# 12_RK3588_MIPI_CSI_HDMI2_1_HDMI.net
KiCad netlist of a schematic drawn in Altium Designer
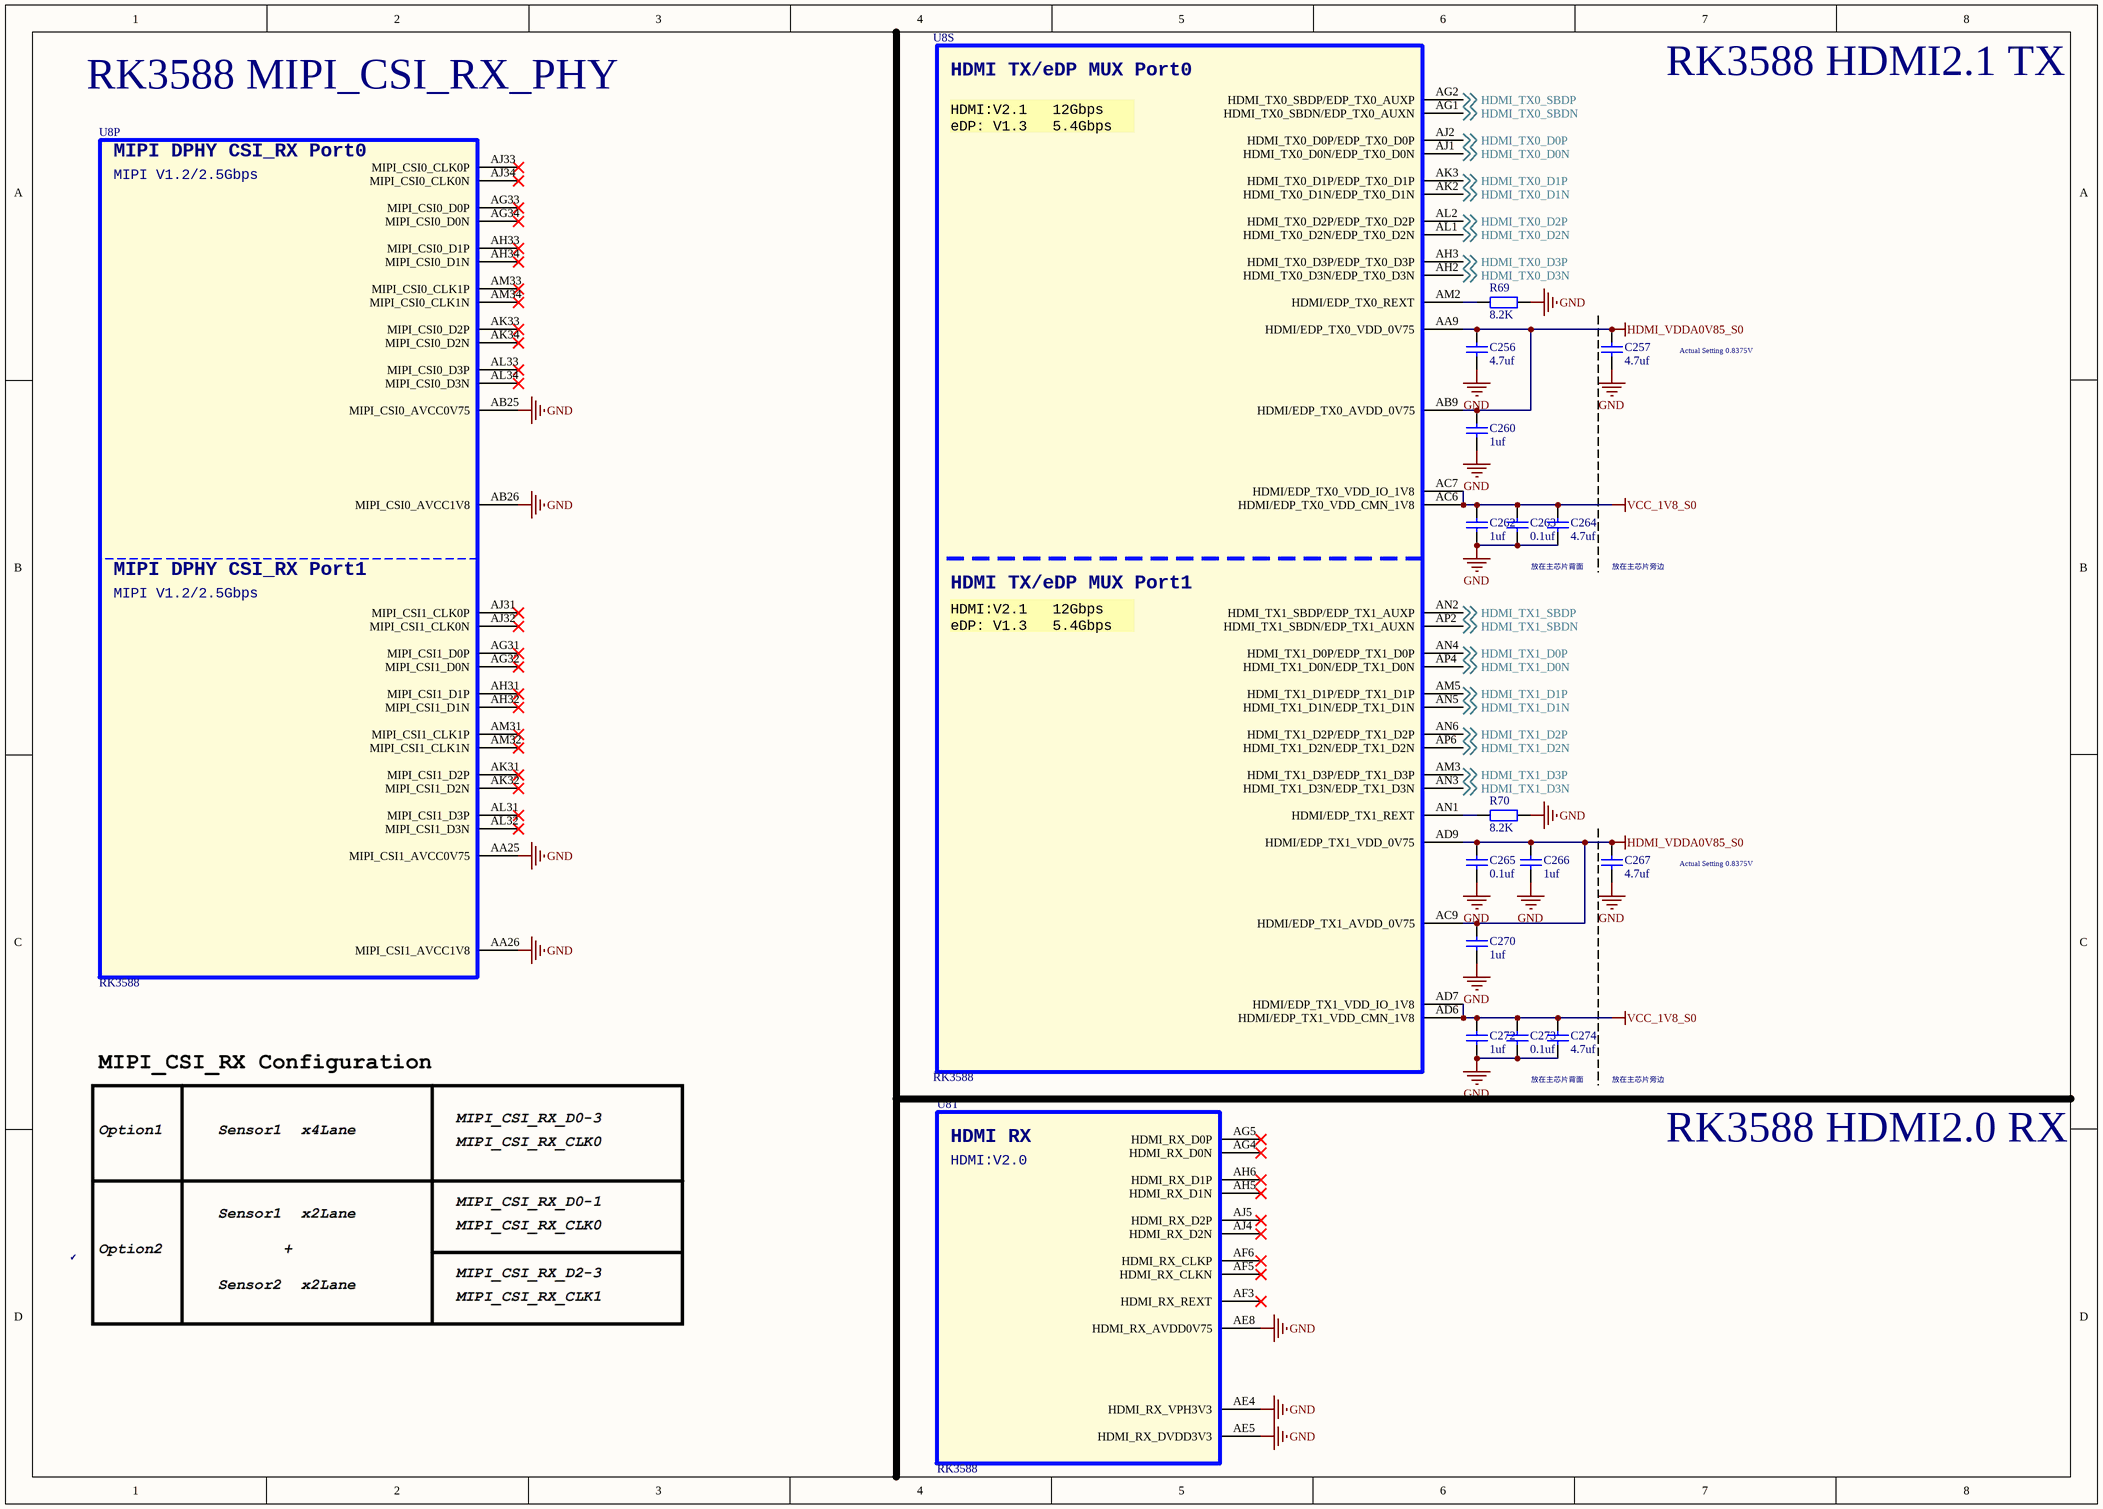
[diagram p0: 12.RK3588_MIPI_CSI_HDMI2.1_HDMI.SchDoc]

(export (version "E")
  (design (tool "Eeschema 10.0.6"))
  (components
    (comp (ref "C256")
      (value "4.7uf")
      (footprint "0.PCB1:C0402_L")
      (description "贴片电容/MLCC电容")
      (libsource (lib "RK3588") (part "C"))
    )
    (comp (ref "C257")
      (value "4.7uf")
      (footprint "0.PCB1:C0402_L")
      (description "贴片电容/MLCC电容")
      (libsource (lib "RK3588") (part "C"))
    )
    (comp (ref "C260")
      (value "1uf")
      (footprint "0.PCB1:C0201_L")
      (description "贴片电容/MLCC电容")
      (libsource (lib "RK3588") (part "C"))
    )
    (comp (ref "C262")
      (value "1uf")
      (footprint "0.PCB1:C0201_L")
      (description "贴片电容/MLCC电容")
      (libsource (lib "RK3588") (part "C"))
    )
    (comp (ref "C263")
      (value "0.1uf")
      (footprint "0.PCB1:C0201_L")
      (description "贴片电容/MLCC电容")
      (libsource (lib "RK3588") (part "C"))
    )
    (comp (ref "C264")
      (value "4.7uf")
      (footprint "0.PCB1:C0201_L")
      (description "贴片电容/MLCC电容")
      (libsource (lib "RK3588") (part "C"))
    )
    (comp (ref "C265")
      (value "0.1uf")
      (footprint "0.PCB1:C0201_L")
      (description "贴片电容/MLCC电容")
      (libsource (lib "RK3588") (part "C"))
    )
    (comp (ref "C266")
      (value "1uf")
      (footprint "0.PCB1:C0201_L")
      (description "贴片电容/MLCC电容")
      (libsource (lib "RK3588") (part "C"))
    )
    (comp (ref "C267")
      (value "4.7uf")
      (footprint "0.PCB1:C0402_L")
      (description "贴片电容/MLCC电容")
      (libsource (lib "RK3588") (part "C"))
    )
    (comp (ref "C270")
      (value "1uf")
      (footprint "0.PCB1:C0201_L")
      (description "贴片电容/MLCC电容")
      (libsource (lib "RK3588") (part "C"))
    )
    (comp (ref "C272")
      (value "1uf")
      (footprint "0.PCB1:C0201_L")
      (description "贴片电容/MLCC电容")
      (libsource (lib "RK3588") (part "C"))
    )
    (comp (ref "C273")
      (value "0.1uf")
      (footprint "0.PCB1:C0201_L")
      (description "贴片电容/MLCC电容")
      (libsource (lib "RK3588") (part "C"))
    )
    (comp (ref "C274")
      (value "4.7uf")
      (footprint "0.PCB1:C0402_L")
      (description "贴片电容/MLCC电容")
      (libsource (lib "RK3588") (part "C"))
    )
    (comp (ref "R69")
      (value "8.2K")
      (footprint "0.PCB1:R0201_L")
      (description "贴片电阻")
      (libsource (lib "RK3588") (part "R"))
    )
    (comp (ref "R70")
      (value "8.2K")
      (footprint "0.PCB1:R0201_L")
      (description "贴片电阻")
      (libsource (lib "RK3588") (part "R"))
    )
    (comp (ref "U8")
      (value "RK3588")
      (footprint "0.PCB1:BGA1088_23R00X23R00X2R00")
      (description "ROCKCHIP SOC")
      (libsource (lib "RK3588") (part "SOC_RK3588"))
    )
  )
  (nets
    (net (code "1") (name "GND") (class "Default")
      (node (ref "C256") (pin "1") (pinfunction "1_1") (pintype "passive"))
      (node (ref "C257") (pin "1") (pinfunction "1_1") (pintype "passive"))
      (node (ref "C260") (pin "1") (pinfunction "1_1") (pintype "passive"))
      (node (ref "C262") (pin "1") (pinfunction "1_1") (pintype "passive"))
      (node (ref "C263") (pin "1") (pinfunction "1_1") (pintype "passive"))
      (node (ref "C264") (pin "1") (pinfunction "1_1") (pintype "passive"))
      (node (ref "C265") (pin "1") (pinfunction "1_1") (pintype "passive"))
      (node (ref "C266") (pin "1") (pinfunction "1_1") (pintype "passive"))
      (node (ref "C267") (pin "1") (pinfunction "1_1") (pintype "passive"))
      (node (ref "C270") (pin "1") (pinfunction "1_1") (pintype "passive"))
      (node (ref "C272") (pin "1") (pinfunction "1_1") (pintype "passive"))
      (node (ref "C273") (pin "1") (pinfunction "1_1") (pintype "passive"))
      (node (ref "C274") (pin "1") (pinfunction "1_1") (pintype "passive"))
      (node (ref "R69") (pin "2") (pinfunction "2_2") (pintype "passive"))
      (node (ref "R70") (pin "2") (pinfunction "2_2") (pintype "passive"))
      (node (ref "U8") (pin "AA25") (pinfunction "MIPI_CSI1_AVCC0V75_AA25") (pintype "passive"))
      (node (ref "U8") (pin "AA26") (pinfunction "MIPI_CSI1_AVCC1V8_AA26") (pintype "passive"))
      (node (ref "U8") (pin "AB25") (pinfunction "MIPI_CSI0_AVCC0V75_AB25") (pintype "passive"))
      (node (ref "U8") (pin "AB26") (pinfunction "MIPI_CSI0_AVCC1V8_AB26") (pintype "passive"))
      (node (ref "U8") (pin "AE4") (pinfunction "HDMI_RX_VPH3V3_AE4") (pintype "passive"))
      (node (ref "U8") (pin "AE5") (pinfunction "HDMI_RX_DVDD3V3_AE5") (pintype "passive"))
      (node (ref "U8") (pin "AE8") (pinfunction "HDMI_RX_AVDD0V75_AE8") (pintype "passive"))
    )
    (net (code "2") (name "HDMI_TX0_D0N") (class "Default")
      (node (ref "U8") (pin "AJ1") (pinfunction "HDMI_TX0_D0N/EDP_TX0_D0N_AJ1") (pintype "passive"))
    )
    (net (code "3") (name "HDMI_TX0_D0P") (class "Default")
      (node (ref "U8") (pin "AJ2") (pinfunction "HDMI_TX0_D0P/EDP_TX0_D0P_AJ2") (pintype "passive"))
    )
    (net (code "4") (name "HDMI_TX0_D1N") (class "Default")
      (node (ref "U8") (pin "AK2") (pinfunction "HDMI_TX0_D1N/EDP_TX0_D1N_AK2") (pintype "passive"))
    )
    (net (code "5") (name "HDMI_TX0_D1P") (class "Default")
      (node (ref "U8") (pin "AK3") (pinfunction "HDMI_TX0_D1P/EDP_TX0_D1P_AK3") (pintype "passive"))
    )
    (net (code "6") (name "HDMI_TX0_D2N") (class "Default")
      (node (ref "U8") (pin "AL1") (pinfunction "HDMI_TX0_D2N/EDP_TX0_D2N_AL1") (pintype "passive"))
    )
    (net (code "7") (name "HDMI_TX0_D2P") (class "Default")
      (node (ref "U8") (pin "AL2") (pinfunction "HDMI_TX0_D2P/EDP_TX0_D2P_AL2") (pintype "passive"))
    )
    (net (code "8") (name "HDMI_TX0_D3N") (class "Default")
      (node (ref "U8") (pin "AH2") (pinfunction "HDMI_TX0_D3N/EDP_TX0_D3N_AH2") (pintype "passive"))
    )
    (net (code "9") (name "HDMI_TX0_D3P") (class "Default")
      (node (ref "U8") (pin "AH3") (pinfunction "HDMI_TX0_D3P/EDP_TX0_D3P_AH3") (pintype "passive"))
    )
    (net (code "10") (name "HDMI_TX0_SBDN") (class "Default")
      (node (ref "U8") (pin "AG1") (pinfunction "HDMI_TX0_SBDN/EDP_TX0_AUXN_AG1") (pintype "passive"))
    )
    (net (code "11") (name "HDMI_TX0_SBDP") (class "Default")
      (node (ref "U8") (pin "AG2") (pinfunction "HDMI_TX0_SBDP/EDP_TX0_AUXP_AG2") (pintype "passive"))
    )
    (net (code "12") (name "HDMI_TX1_D0N") (class "Default")
      (node (ref "U8") (pin "AP4") (pinfunction "HDMI_TX1_D0N/EDP_TX1_D0N_AP4") (pintype "passive"))
    )
    (net (code "13") (name "HDMI_TX1_D0P") (class "Default")
      (node (ref "U8") (pin "AN4") (pinfunction "HDMI_TX1_D0P/EDP_TX1_D0P_AN4") (pintype "passive"))
    )
    (net (code "14") (name "HDMI_TX1_D1N") (class "Default")
      (node (ref "U8") (pin "AN5") (pinfunction "HDMI_TX1_D1N/EDP_TX1_D1N_AN5") (pintype "passive"))
    )
    (net (code "15") (name "HDMI_TX1_D1P") (class "Default")
      (node (ref "U8") (pin "AM5") (pinfunction "HDMI_TX1_D1P/EDP_TX1_D1P_AM5") (pintype "passive"))
    )
    (net (code "16") (name "HDMI_TX1_D2N") (class "Default")
      (node (ref "U8") (pin "AP6") (pinfunction "HDMI_TX1_D2N/EDP_TX1_D2N_AP6") (pintype "passive"))
    )
    (net (code "17") (name "HDMI_TX1_D2P") (class "Default")
      (node (ref "U8") (pin "AN6") (pinfunction "HDMI_TX1_D2P/EDP_TX1_D2P_AN6") (pintype "passive"))
    )
    (net (code "18") (name "HDMI_TX1_D3N") (class "Default")
      (node (ref "U8") (pin "AN3") (pinfunction "HDMI_TX1_D3N/EDP_TX1_D3N_AN3") (pintype "passive"))
    )
    (net (code "19") (name "HDMI_TX1_D3P") (class "Default")
      (node (ref "U8") (pin "AM3") (pinfunction "HDMI_TX1_D3P/EDP_TX1_D3P_AM3") (pintype "passive"))
    )
    (net (code "20") (name "HDMI_TX1_SBDN") (class "Default")
      (node (ref "U8") (pin "AP2") (pinfunction "HDMI_TX1_SBDN/EDP_TX1_AUXN_AP2") (pintype "passive"))
    )
    (net (code "21") (name "HDMI_TX1_SBDP") (class "Default")
      (node (ref "U8") (pin "AN2") (pinfunction "HDMI_TX1_SBDP/EDP_TX1_AUXP_AN2") (pintype "passive"))
    )
    (net (code "22") (name "HDMI_VDDA0V85_S0") (class "Default")
      (node (ref "C256") (pin "2") (pinfunction "2_2") (pintype "passive"))
      (node (ref "C257") (pin "2") (pinfunction "2_2") (pintype "passive"))
      (node (ref "C260") (pin "2") (pinfunction "2_2") (pintype "passive"))
      (node (ref "C265") (pin "2") (pinfunction "2_2") (pintype "passive"))
      (node (ref "C266") (pin "2") (pinfunction "2_2") (pintype "passive"))
      (node (ref "C267") (pin "2") (pinfunction "2_2") (pintype "passive"))
      (node (ref "C270") (pin "2") (pinfunction "2_2") (pintype "passive"))
      (node (ref "U8") (pin "AA9") (pinfunction "HDMI/EDP_TX0_VDD_0V75_AA9") (pintype "passive"))
      (node (ref "U8") (pin "AB9") (pinfunction "HDMI/EDP_TX0_AVDD_0V75_AB9") (pintype "passive"))
      (node (ref "U8") (pin "AC9") (pinfunction "HDMI/EDP_TX1_AVDD_0V75_AC9") (pintype "passive"))
      (node (ref "U8") (pin "AD9") (pinfunction "HDMI/EDP_TX1_VDD_0V75_AD9") (pintype "passive"))
    )
    (net (code "23") (name "Net-(U8S-HDMI{slash}EDP_TX0_REXT)") (class "Default")
      (node (ref "R69") (pin "1") (pinfunction "1_1") (pintype "passive"))
      (node (ref "U8") (pin "AM2") (pinfunction "HDMI/EDP_TX0_REXT_AM2") (pintype "passive"))
    )
    (net (code "24") (name "Net-(U8S-HDMI{slash}EDP_TX1_REXT)") (class "Default")
      (node (ref "R70") (pin "1") (pinfunction "1_1") (pintype "passive"))
      (node (ref "U8") (pin "AN1") (pinfunction "HDMI/EDP_TX1_REXT_AN1") (pintype "passive"))
    )
    (net (code "25") (name "VCC_1V8_S0") (class "Default")
      (node (ref "C262") (pin "2") (pinfunction "2_2") (pintype "passive"))
      (node (ref "C263") (pin "2") (pinfunction "2_2") (pintype "passive"))
      (node (ref "C264") (pin "2") (pinfunction "2_2") (pintype "passive"))
      (node (ref "C272") (pin "2") (pinfunction "2_2") (pintype "passive"))
      (node (ref "C273") (pin "2") (pinfunction "2_2") (pintype "passive"))
      (node (ref "C274") (pin "2") (pinfunction "2_2") (pintype "passive"))
      (node (ref "U8") (pin "AC6") (pinfunction "HDMI/EDP_TX0_VDD_CMN_1V8_AC6") (pintype "passive"))
      (node (ref "U8") (pin "AC7") (pinfunction "HDMI/EDP_TX0_VDD_IO_1V8_AC7") (pintype "passive"))
      (node (ref "U8") (pin "AD6") (pinfunction "HDMI/EDP_TX1_VDD_CMN_1V8_AD6") (pintype "passive"))
      (node (ref "U8") (pin "AD7") (pinfunction "HDMI/EDP_TX1_VDD_IO_1V8_AD7") (pintype "passive"))
    )
    (net (code "26") (name "unconnected-(U8P-MIPI_CSI0_CLK0N-PadAJ34)") (class "Default")
      (node (ref "U8") (pin "AJ34") (pinfunction "MIPI_CSI0_CLK0N_AJ34") (pintype "passive+no_connect"))
    )
    (net (code "27") (name "unconnected-(U8P-MIPI_CSI0_CLK0P-PadAJ33)") (class "Default")
      (node (ref "U8") (pin "AJ33") (pinfunction "MIPI_CSI0_CLK0P_AJ33") (pintype "passive+no_connect"))
    )
    (net (code "28") (name "unconnected-(U8P-MIPI_CSI0_CLK1N-PadAM34)") (class "Default")
      (node (ref "U8") (pin "AM34") (pinfunction "MIPI_CSI0_CLK1N_AM34") (pintype "passive+no_connect"))
    )
    (net (code "29") (name "unconnected-(U8P-MIPI_CSI0_CLK1P-PadAM33)") (class "Default")
      (node (ref "U8") (pin "AM33") (pinfunction "MIPI_CSI0_CLK1P_AM33") (pintype "passive+no_connect"))
    )
    (net (code "30") (name "unconnected-(U8P-MIPI_CSI0_D0N-PadAG34)") (class "Default")
      (node (ref "U8") (pin "AG34") (pinfunction "MIPI_CSI0_D0N_AG34") (pintype "passive+no_connect"))
    )
    (net (code "31") (name "unconnected-(U8P-MIPI_CSI0_D0P-PadAG33)") (class "Default")
      (node (ref "U8") (pin "AG33") (pinfunction "MIPI_CSI0_D0P_AG33") (pintype "passive+no_connect"))
    )
    (net (code "32") (name "unconnected-(U8P-MIPI_CSI0_D1N-PadAH34)") (class "Default")
      (node (ref "U8") (pin "AH34") (pinfunction "MIPI_CSI0_D1N_AH34") (pintype "passive+no_connect"))
    )
    (net (code "33") (name "unconnected-(U8P-MIPI_CSI0_D1P-PadAH33)") (class "Default")
      (node (ref "U8") (pin "AH33") (pinfunction "MIPI_CSI0_D1P_AH33") (pintype "passive+no_connect"))
    )
    (net (code "34") (name "unconnected-(U8P-MIPI_CSI0_D2N-PadAK34)") (class "Default")
      (node (ref "U8") (pin "AK34") (pinfunction "MIPI_CSI0_D2N_AK34") (pintype "passive+no_connect"))
    )
    (net (code "35") (name "unconnected-(U8P-MIPI_CSI0_D2P-PadAK33)") (class "Default")
      (node (ref "U8") (pin "AK33") (pinfunction "MIPI_CSI0_D2P_AK33") (pintype "passive+no_connect"))
    )
    (net (code "36") (name "unconnected-(U8P-MIPI_CSI0_D3N-PadAL34)") (class "Default")
      (node (ref "U8") (pin "AL34") (pinfunction "MIPI_CSI0_D3N_AL34") (pintype "passive+no_connect"))
    )
    (net (code "37") (name "unconnected-(U8P-MIPI_CSI0_D3P-PadAL33)") (class "Default")
      (node (ref "U8") (pin "AL33") (pinfunction "MIPI_CSI0_D3P_AL33") (pintype "passive+no_connect"))
    )
    (net (code "38") (name "unconnected-(U8P-MIPI_CSI1_CLK0N-PadAJ32)") (class "Default")
      (node (ref "U8") (pin "AJ32") (pinfunction "MIPI_CSI1_CLK0N_AJ32") (pintype "passive+no_connect"))
    )
    (net (code "39") (name "unconnected-(U8P-MIPI_CSI1_CLK0P-PadAJ31)") (class "Default")
      (node (ref "U8") (pin "AJ31") (pinfunction "MIPI_CSI1_CLK0P_AJ31") (pintype "passive+no_connect"))
    )
    (net (code "40") (name "unconnected-(U8P-MIPI_CSI1_CLK1N-PadAM32)") (class "Default")
      (node (ref "U8") (pin "AM32") (pinfunction "MIPI_CSI1_CLK1N_AM32") (pintype "passive+no_connect"))
    )
    (net (code "41") (name "unconnected-(U8P-MIPI_CSI1_CLK1P-PadAM31)") (class "Default")
      (node (ref "U8") (pin "AM31") (pinfunction "MIPI_CSI1_CLK1P_AM31") (pintype "passive+no_connect"))
    )
    (net (code "42") (name "unconnected-(U8P-MIPI_CSI1_D0N-PadAG32)") (class "Default")
      (node (ref "U8") (pin "AG32") (pinfunction "MIPI_CSI1_D0N_AG32") (pintype "passive+no_connect"))
    )
    (net (code "43") (name "unconnected-(U8P-MIPI_CSI1_D0P-PadAG31)") (class "Default")
      (node (ref "U8") (pin "AG31") (pinfunction "MIPI_CSI1_D0P_AG31") (pintype "passive+no_connect"))
    )
    (net (code "44") (name "unconnected-(U8P-MIPI_CSI1_D1N-PadAH32)") (class "Default")
      (node (ref "U8") (pin "AH32") (pinfunction "MIPI_CSI1_D1N_AH32") (pintype "passive+no_connect"))
    )
    (net (code "45") (name "unconnected-(U8P-MIPI_CSI1_D1P-PadAH31)") (class "Default")
      (node (ref "U8") (pin "AH31") (pinfunction "MIPI_CSI1_D1P_AH31") (pintype "passive+no_connect"))
    )
    (net (code "46") (name "unconnected-(U8P-MIPI_CSI1_D2N-PadAK32)") (class "Default")
      (node (ref "U8") (pin "AK32") (pinfunction "MIPI_CSI1_D2N_AK32") (pintype "passive+no_connect"))
    )
    (net (code "47") (name "unconnected-(U8P-MIPI_CSI1_D2P-PadAK31)") (class "Default")
      (node (ref "U8") (pin "AK31") (pinfunction "MIPI_CSI1_D2P_AK31") (pintype "passive+no_connect"))
    )
    (net (code "48") (name "unconnected-(U8P-MIPI_CSI1_D3N-PadAL32)") (class "Default")
      (node (ref "U8") (pin "AL32") (pinfunction "MIPI_CSI1_D3N_AL32") (pintype "passive+no_connect"))
    )
    (net (code "49") (name "unconnected-(U8P-MIPI_CSI1_D3P-PadAL31)") (class "Default")
      (node (ref "U8") (pin "AL31") (pinfunction "MIPI_CSI1_D3P_AL31") (pintype "passive+no_connect"))
    )
    (net (code "50") (name "unconnected-(U8T-HDMI_RX_CLKN-PadAF5)") (class "Default")
      (node (ref "U8") (pin "AF5") (pinfunction "HDMI_RX_CLKN_AF5") (pintype "passive+no_connect"))
    )
    (net (code "51") (name "unconnected-(U8T-HDMI_RX_CLKP-PadAF6)") (class "Default")
      (node (ref "U8") (pin "AF6") (pinfunction "HDMI_RX_CLKP_AF6") (pintype "passive+no_connect"))
    )
    (net (code "52") (name "unconnected-(U8T-HDMI_RX_D0N-PadAG4)") (class "Default")
      (node (ref "U8") (pin "AG4") (pinfunction "HDMI_RX_D0N_AG4") (pintype "passive+no_connect"))
    )
    (net (code "53") (name "unconnected-(U8T-HDMI_RX_D0P-PadAG5)") (class "Default")
      (node (ref "U8") (pin "AG5") (pinfunction "HDMI_RX_D0P_AG5") (pintype "passive+no_connect"))
    )
    (net (code "54") (name "unconnected-(U8T-HDMI_RX_D1N-PadAH5)") (class "Default")
      (node (ref "U8") (pin "AH5") (pinfunction "HDMI_RX_D1N_AH5") (pintype "passive+no_connect"))
    )
    (net (code "55") (name "unconnected-(U8T-HDMI_RX_D1P-PadAH6)") (class "Default")
      (node (ref "U8") (pin "AH6") (pinfunction "HDMI_RX_D1P_AH6") (pintype "passive+no_connect"))
    )
    (net (code "56") (name "unconnected-(U8T-HDMI_RX_D2N-PadAJ4)") (class "Default")
      (node (ref "U8") (pin "AJ4") (pinfunction "HDMI_RX_D2N_AJ4") (pintype "passive+no_connect"))
    )
    (net (code "57") (name "unconnected-(U8T-HDMI_RX_D2P-PadAJ5)") (class "Default")
      (node (ref "U8") (pin "AJ5") (pinfunction "HDMI_RX_D2P_AJ5") (pintype "passive+no_connect"))
    )
    (net (code "58") (name "unconnected-(U8T-HDMI_RX_REXT-PadAF3)") (class "Default")
      (node (ref "U8") (pin "AF3") (pinfunction "HDMI_RX_REXT_AF3") (pintype "passive+no_connect"))
    )
  )
)
